# Power_Regulators_RF_4.net
KiCad netlist of a schematic drawn in Altium Designer
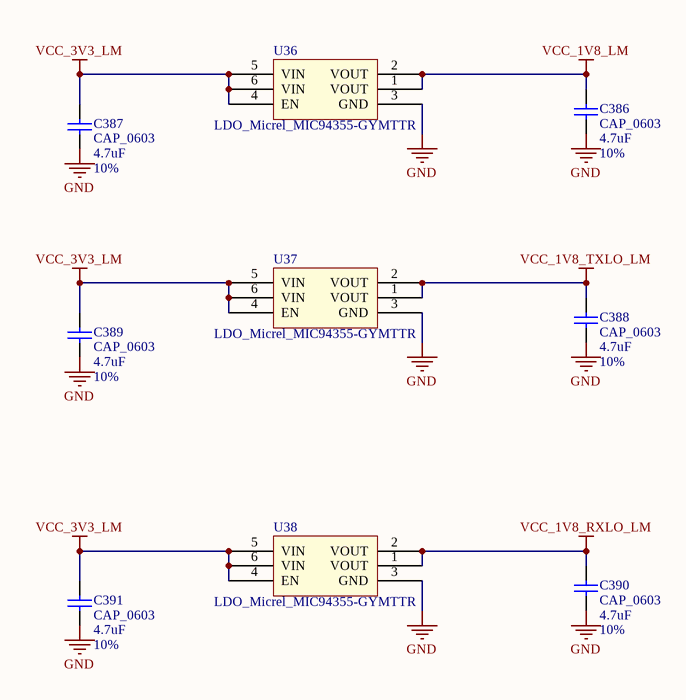
[diagram p0: Power_Regulators_RF_4.SchDoc]

(export (version "E")
  (design (tool "Eeschema 10.0.6"))
  (components
    (comp (ref "C386")
      (value "CAP_0603")
      (footprint "CAPC0603(1608)100_N")
      (description "4.7uF, ceramic, 10%, 10V X5R, 0603")
      (fields
        (field (name "ALTIUM_VALUE") "4.7uF")
        (field (name "TOLERANCE") "10%")
        (field (name "PART NUMBER") "LMK107BJ475KA-T")
        (field (name "MANUFACTURER") "Taiyo Yuden")
      )
      (libsource (lib "COMRAD_Database") (part "CAP_0603"))
    )
    (comp (ref "C387")
      (value "CAP_0603")
      (footprint "CAPC0603(1608)100_N")
      (description "4.7uF, ceramic, 10%, 10V X5R, 0603")
      (fields
        (field (name "ALTIUM_VALUE") "4.7uF")
        (field (name "TOLERANCE") "10%")
        (field (name "PART NUMBER") "LMK107BJ475KA-T")
        (field (name "MANUFACTURER") "Taiyo Yuden")
      )
      (libsource (lib "COMRAD_Database") (part "CAP_0603"))
    )
    (comp (ref "C388")
      (value "CAP_0603")
      (footprint "CAPC0603(1608)100_N")
      (description "4.7uF, ceramic, 10%, 10V X5R, 0603")
      (fields
        (field (name "ALTIUM_VALUE") "4.7uF")
        (field (name "TOLERANCE") "10%")
        (field (name "PART NUMBER") "LMK107BJ475KA-T")
        (field (name "MANUFACTURER") "Taiyo Yuden")
      )
      (libsource (lib "COMRAD_Database") (part "CAP_0603"))
    )
    (comp (ref "C389")
      (value "CAP_0603")
      (footprint "CAPC0603(1608)100_N")
      (description "4.7uF, ceramic, 10%, 10V X5R, 0603")
      (fields
        (field (name "ALTIUM_VALUE") "4.7uF")
        (field (name "TOLERANCE") "10%")
        (field (name "PART NUMBER") "LMK107BJ475KA-T")
        (field (name "MANUFACTURER") "Taiyo Yuden")
      )
      (libsource (lib "COMRAD_Database") (part "CAP_0603"))
    )
    (comp (ref "C390")
      (value "CAP_0603")
      (footprint "CAPC0603(1608)100_N")
      (description "4.7uF, ceramic, 10%, 10V X5R, 0603")
      (fields
        (field (name "ALTIUM_VALUE") "4.7uF")
        (field (name "TOLERANCE") "10%")
        (field (name "PART NUMBER") "LMK107BJ475KA-T")
        (field (name "MANUFACTURER") "Taiyo Yuden")
      )
      (libsource (lib "COMRAD_Database") (part "CAP_0603"))
    )
    (comp (ref "C391")
      (value "CAP_0603")
      (footprint "CAPC0603(1608)100_N")
      (description "4.7uF, ceramic, 10%, 10V X5R, 0603")
      (fields
        (field (name "ALTIUM_VALUE") "4.7uF")
        (field (name "TOLERANCE") "10%")
        (field (name "PART NUMBER") "LMK107BJ475KA-T")
        (field (name "MANUFACTURER") "Taiyo Yuden")
      )
      (libsource (lib "COMRAD_Database") (part "CAP_0603"))
    )
    (comp (ref "U36")
      (value "LDO_Micrel_MIC94355-GYMTTR")
      (footprint "LDO_Micrel_MIC94325YMTTR_TDFN-6")
      (description "IC REG LDO 1.8V .5A 6TDFN")
      (fields (field (name "PART NUMBER") "MIC94355-GYMT TR") (field (name "MANUFACTURER") "Micrel Inc"))
      (libsource (lib "COMRAD_Database") (part "LDO_Micrel_MIC94355-GYMTTR"))
    )
    (comp (ref "U37")
      (value "LDO_Micrel_MIC94355-GYMTTR")
      (footprint "LDO_Micrel_MIC94325YMTTR_TDFN-6")
      (description "IC REG LDO 1.8V .5A 6TDFN")
      (fields (field (name "PART NUMBER") "MIC94355-GYMT TR") (field (name "MANUFACTURER") "Micrel Inc"))
      (libsource (lib "COMRAD_Database") (part "LDO_Micrel_MIC94355-GYMTTR"))
    )
    (comp (ref "U38")
      (value "LDO_Micrel_MIC94355-GYMTTR")
      (footprint "LDO_Micrel_MIC94325YMTTR_TDFN-6")
      (description "IC REG LDO 1.8V .5A 6TDFN")
      (fields (field (name "PART NUMBER") "MIC94355-GYMT TR") (field (name "MANUFACTURER") "Micrel Inc"))
      (libsource (lib "COMRAD_Database") (part "LDO_Micrel_MIC94355-GYMTTR"))
    )
  )
  (nets
    (net (code "1") (name "GND") (class "Default")
      (node (ref "C386") (pin "1") (pinfunction "1_1") (pintype "passive"))
      (node (ref "C387") (pin "1") (pinfunction "1_1") (pintype "passive"))
      (node (ref "C388") (pin "1") (pinfunction "1_1") (pintype "passive"))
      (node (ref "C389") (pin "1") (pinfunction "1_1") (pintype "passive"))
      (node (ref "C390") (pin "1") (pinfunction "1_1") (pintype "passive"))
      (node (ref "C391") (pin "1") (pinfunction "1_1") (pintype "passive"))
      (node (ref "U36") (pin "3") (pinfunction "GND_3") (pintype "passive"))
      (node (ref "U37") (pin "3") (pinfunction "GND_3") (pintype "passive"))
      (node (ref "U38") (pin "3") (pinfunction "GND_3") (pintype "passive"))
    )
    (net (code "2") (name "VCC_1V8_LM") (class "Default")
      (node (ref "C386") (pin "2") (pinfunction "2_2") (pintype "passive"))
      (node (ref "U36") (pin "1") (pinfunction "VOUT_1") (pintype "passive"))
      (node (ref "U36") (pin "2") (pinfunction "VOUT_2") (pintype "passive"))
    )
    (net (code "3") (name "VCC_1V8_RXLO_LM") (class "Default")
      (node (ref "C390") (pin "2") (pinfunction "2_2") (pintype "passive"))
      (node (ref "U38") (pin "1") (pinfunction "VOUT_1") (pintype "passive"))
      (node (ref "U38") (pin "2") (pinfunction "VOUT_2") (pintype "passive"))
    )
    (net (code "4") (name "VCC_1V8_TXLO_LM") (class "Default")
      (node (ref "C388") (pin "2") (pinfunction "2_2") (pintype "passive"))
      (node (ref "U37") (pin "1") (pinfunction "VOUT_1") (pintype "passive"))
      (node (ref "U37") (pin "2") (pinfunction "VOUT_2") (pintype "passive"))
    )
    (net (code "5") (name "VCC_3V3_LM") (class "Default")
      (node (ref "C387") (pin "2") (pinfunction "2_2") (pintype "passive"))
      (node (ref "C389") (pin "2") (pinfunction "2_2") (pintype "passive"))
      (node (ref "C391") (pin "2") (pinfunction "2_2") (pintype "passive"))
      (node (ref "U36") (pin "4") (pinfunction "EN_4") (pintype "passive"))
      (node (ref "U36") (pin "5") (pinfunction "VIN_5") (pintype "passive"))
      (node (ref "U36") (pin "6") (pinfunction "VIN_6") (pintype "passive"))
      (node (ref "U37") (pin "4") (pinfunction "EN_4") (pintype "passive"))
      (node (ref "U37") (pin "5") (pinfunction "VIN_5") (pintype "passive"))
      (node (ref "U37") (pin "6") (pinfunction "VIN_6") (pintype "passive"))
      (node (ref "U38") (pin "4") (pinfunction "EN_4") (pintype "passive"))
      (node (ref "U38") (pin "5") (pinfunction "VIN_5") (pintype "passive"))
      (node (ref "U38") (pin "6") (pinfunction "VIN_6") (pintype "passive"))
    )
  )
)
